# STM32F103VE.net
KiCad netlist of a schematic drawn in Altium Designer
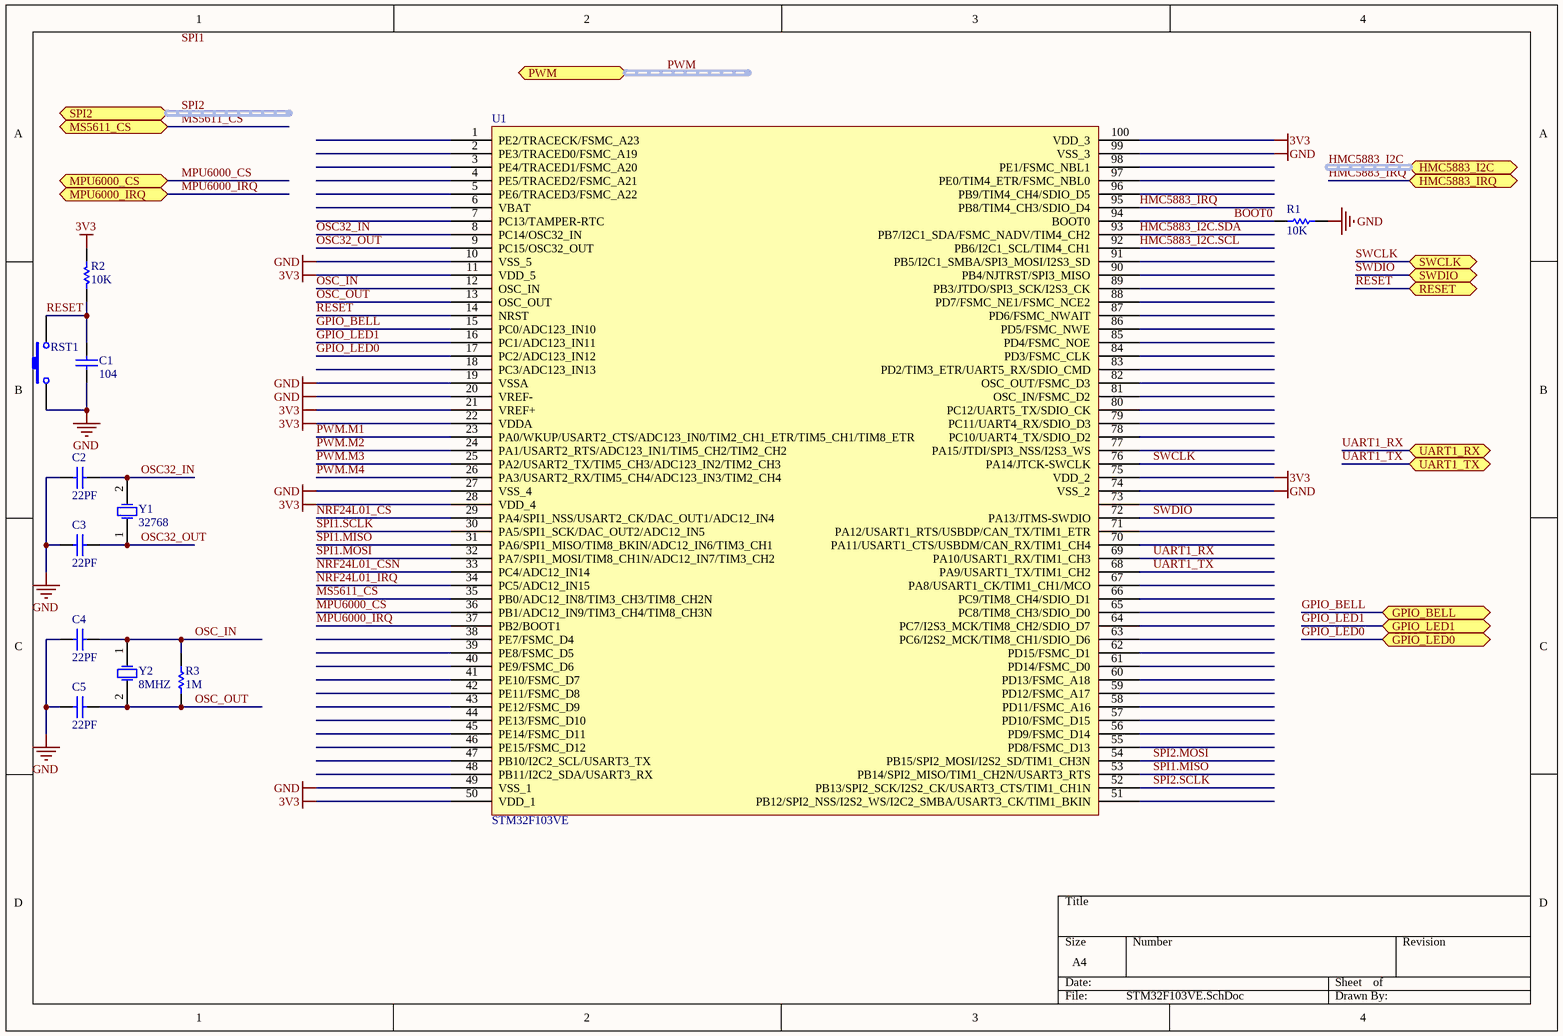
[diagram p0: STM32F103VE.SchDoc]

(export (version "E")
  (design (tool "Eeschema 10.0.6"))
  (components
    (comp (ref "C1")
      (value "104")
      (footprint "RC0805")
      (description "Capacitor")
      (fields (field (name "Comment") "Cap") (field (name "PUBLISHER") "Altium Limited"))
      (libsource (lib "Miscellaneous Devices") (part "Cap"))
    )
    (comp (ref "C2")
      (value "22PF")
      (footprint "RC0805")
      (description "Capacitor")
      (fields (field (name "Comment") "Cap") (field (name "PUBLISHER") "Altium Limited"))
      (libsource (lib "Miscellaneous Devices") (part "Cap"))
    )
    (comp (ref "C3")
      (value "22PF")
      (footprint "RC0805")
      (description "Capacitor")
      (fields (field (name "Comment") "Cap") (field (name "PUBLISHER") "Altium Limited"))
      (libsource (lib "Miscellaneous Devices") (part "Cap"))
    )
    (comp (ref "C4")
      (value "22PF")
      (footprint "RC0805")
      (description "Capacitor")
      (fields (field (name "Comment") "Cap") (field (name "PUBLISHER") "Altium Limited"))
      (libsource (lib "Miscellaneous Devices") (part "Cap"))
    )
    (comp (ref "C5")
      (value "22PF")
      (footprint "RC0805")
      (description "Capacitor")
      (fields (field (name "Comment") "Cap") (field (name "PUBLISHER") "Altium Limited"))
      (libsource (lib "Miscellaneous Devices") (part "Cap"))
    )
    (comp (ref "R1")
      (value "10K")
      (footprint "RC0805")
      (description "Resistor")
      (fields (field (name "Comment") "Res1") (field (name "PUBLISHER") "Altium Limited"))
      (libsource (lib "Miscellaneous Devices") (part "Res1"))
    )
    (comp (ref "R2")
      (value "10K")
      (footprint "RC0805")
      (description "Resistor")
      (fields (field (name "Comment") "Res1") (field (name "PUBLISHER") "Altium Limited"))
      (libsource (lib "Miscellaneous Devices") (part "Res1"))
    )
    (comp (ref "R3")
      (value "1M")
      (footprint "RC0805")
      (description "Resistor")
      (fields (field (name "Comment") "Res1") (field (name "PUBLISHER") "Altium Limited"))
      (libsource (lib "Miscellaneous Devices") (part "Res1"))
    )
    (comp (ref "RST1")
      (value "SW-PB")
      (footprint "KEY2*2(COMMON)")
      (description "Switch")
      (fields (field (name "PUBLISHER") "Altium Limited"))
      (libsource (lib "Miscellaneous Devices") (part "SW-PB"))
    )
    (comp (ref "U1") (value "STM32F103VE") (libsource (lib "Schlib1") (part "STM32F103VE")))
    (comp (ref "Y1")
      (value "32768")
      (footprint "XTAL32")
      (description "Crystal Oscillator")
      (fields (field (name "PUBLISHER") "Altium Limited"))
      (libsource (lib "Miscellaneous Devices") (part "XTAL"))
    )
    (comp (ref "Y2")
      (value "8MHZ")
      (footprint "OSC")
      (description "Crystal Oscillator")
      (fields (field (name "PUBLISHER") "Altium Limited"))
      (libsource (lib "底板封装库") (part "XTAL"))
    )
  )
  (nets
    (net (code "4") (name "/BOOT0") (class "Default")
      (node (ref "R1") (pin "2") (pinfunction "2_2") (pintype "passive"))
      (node (ref "U1") (pin "94") (pinfunction "BOOT0_94") (pintype "passive"))
    )
    (net (code "5") (name "/GPIO_BELL") (class "Default")
      (node (ref "U1") (pin "15") (pinfunction "PC0/ADC123_IN10_15") (pintype "passive"))
    )
    (net (code "6") (name "/GPIO_LED0") (class "Default")
      (node (ref "U1") (pin "17") (pinfunction "PC2/ADC123_IN12_17") (pintype "passive"))
    )
    (net (code "7") (name "/GPIO_LED1") (class "Default")
      (node (ref "U1") (pin "16") (pinfunction "PC1/ADC123_IN11_16") (pintype "passive"))
    )
    (net (code "8") (name "/HMC5883_I2C.SCL") (class "Default")
      (node (ref "U1") (pin "92") (pinfunction "PB6/I2C1_SCL/TIM4_CH1_92") (pintype "passive"))
    )
    (net (code "9") (name "/HMC5883_I2C.SDA") (class "Default")
      (node (ref "U1") (pin "93") (pinfunction "PB7/I2C1_SDA/FSMC_NADV/TIM4_CH2_93") (pintype "passive"))
    )
    (net (code "10") (name "/HMC5883_IRQ") (class "Default")
      (node (ref "U1") (pin "95") (pinfunction "PB8/TIM4_CH3/SDIO_D4_95") (pintype "passive"))
    )
    (net (code "11") (name "/MPU6000_CS") (class "Default")
      (node (ref "U1") (pin "36") (pinfunction "PB1/ADC12_IN9/TIM3_CH4/TIM8_CH3N_36") (pintype "passive"))
    )
    (net (code "12") (name "/MPU6000_IRQ") (class "Default")
      (node (ref "U1") (pin "37") (pinfunction "PB2/BOOT1_37") (pintype "passive"))
    )
    (net (code "13") (name "/MS5611_CS") (class "Default")
      (node (ref "U1") (pin "35") (pinfunction "PB0/ADC12_IN8/TIM3_CH3/TIM8_CH2N_35") (pintype "passive"))
    )
    (net (code "14") (name "/NRF24L01_CS") (class "Default")
      (node (ref "U1") (pin "29") (pinfunction "PA4/SPI1_NSS/USART2_CK/DAC_OUT1/ADC12_IN4_29") (pintype "passive"))
    )
    (net (code "15") (name "/NRF24L01_CSN") (class "Default")
      (node (ref "U1") (pin "33") (pinfunction "PC4/ADC12_IN14_33") (pintype "passive"))
    )
    (net (code "16") (name "/NRF24L01_IRQ") (class "Default")
      (node (ref "U1") (pin "34") (pinfunction "PC5/ADC12_IN15_34") (pintype "passive"))
    )
    (net (code "17") (name "/OSC32_IN") (class "Default")
      (node (ref "C2") (pin "2") (pinfunction "2_2") (pintype "passive"))
      (node (ref "U1") (pin "8") (pinfunction "PC14/OSC32_IN_8") (pintype "passive"))
      (node (ref "Y1") (pin "2") (pinfunction "OSC2_2") (pintype "passive"))
    )
    (net (code "18") (name "/OSC32_OUT") (class "Default")
      (node (ref "C3") (pin "2") (pinfunction "2_2") (pintype "passive"))
      (node (ref "U1") (pin "9") (pinfunction "PC15/OSC32_OUT_9") (pintype "passive"))
      (node (ref "Y1") (pin "1") (pinfunction "OSC1_1") (pintype "passive"))
    )
    (net (code "19") (name "/OSC_IN") (class "Default")
      (node (ref "C4") (pin "2") (pinfunction "2_2") (pintype "passive"))
      (node (ref "R3") (pin "2") (pinfunction "2_2") (pintype "passive"))
      (node (ref "U1") (pin "12") (pinfunction "OSC_IN_12") (pintype "passive"))
      (node (ref "Y2") (pin "1") (pinfunction "OSC1_1") (pintype "passive"))
    )
    (net (code "20") (name "/OSC_OUT") (class "Default")
      (node (ref "C5") (pin "2") (pinfunction "2_2") (pintype "passive"))
      (node (ref "R3") (pin "1") (pinfunction "1_1") (pintype "passive"))
      (node (ref "U1") (pin "13") (pinfunction "OSC_OUT_13") (pintype "passive"))
      (node (ref "Y2") (pin "2") (pinfunction "OSC2_2") (pintype "passive"))
    )
    (net (code "21") (name "/PWM.M1") (class "Default")
      (node (ref "U1") (pin "23") (pinfunction "PA0/WKUP/USART2_CTS/ADC123_IN0/TIM2_CH1_ETR/TIM5_CH1/TIM8_ETR_23") (pintype "passive"))
    )
    (net (code "22") (name "/PWM.M2") (class "Default")
      (node (ref "U1") (pin "24") (pinfunction "PA1/USART2_RTS/ADC123_IN1/TIM5_CH2/TIM2_CH2_24") (pintype "passive"))
    )
    (net (code "23") (name "/PWM.M3") (class "Default")
      (node (ref "U1") (pin "25") (pinfunction "PA2/USART2_TX/TIM5_CH3/ADC123_IN2/TIM2_CH3_25") (pintype "passive"))
    )
    (net (code "24") (name "/PWM.M4") (class "Default")
      (node (ref "U1") (pin "26") (pinfunction "PA3/USART2_RX/TIM5_CH4/ADC123_IN3/TIM2_CH4_26") (pintype "passive"))
    )
    (net (code "25") (name "/RESET") (class "Default")
      (node (ref "C1") (pin "1") (pinfunction "1_1") (pintype "passive"))
      (node (ref "R2") (pin "1") (pinfunction "1_1") (pintype "passive"))
      (node (ref "RST1") (pin "1") (pinfunction "1_1") (pintype "passive"))
      (node (ref "U1") (pin "14") (pinfunction "NRST_14") (pintype "passive"))
    )
    (net (code "27") (name "/SPI1.MISO") (class "Default")
      (node (ref "U1") (pin "31") (pinfunction "PA6/SPI1_MISO/TIM8_BKIN/ADC12_IN6/TIM3_CH1_31") (pintype "passive"))
      (node (ref "U1") (pin "53") (pinfunction "PB14/SPI2_MISO/TIM1_CH2N/USART3_RTS_53") (pintype "passive"))
    )
    (net (code "28") (name "/SPI1.MOSI") (class "Default")
      (node (ref "U1") (pin "32") (pinfunction "PA7/SPI1_MOSI/TIM8_CH1N/ADC12_IN7/TIM3_CH2_32") (pintype "passive"))
    )
    (net (code "29") (name "/SPI1.SCLK") (class "Default")
      (node (ref "U1") (pin "30") (pinfunction "PA5/SPI1_SCK/DAC_OUT2/ADC12_IN5_30") (pintype "passive"))
    )
    (net (code "30") (name "/SPI2.MOSI") (class "Default")
      (node (ref "U1") (pin "54") (pinfunction "PB15/SPI2_MOSI/I2S2_SD/TIM1_CH3N_54") (pintype "passive"))
    )
    (net (code "31") (name "/SPI2.SCLK") (class "Default")
      (node (ref "U1") (pin "52") (pinfunction "PB13/SPI2_SCK/I2S2_CK/USART3_CTS/TIM1_CH1N_52") (pintype "passive"))
    )
    (net (code "32") (name "/SWCLK") (class "Default")
      (node (ref "U1") (pin "76") (pinfunction "PA14/JTCK-SWCLK_76") (pintype "passive"))
    )
    (net (code "33") (name "/SWDIO") (class "Default")
      (node (ref "U1") (pin "72") (pinfunction "PA13/JTMS-SWDIO_72") (pintype "passive"))
    )
    (net (code "34") (name "/UART1_RX") (class "Default")
      (node (ref "U1") (pin "69") (pinfunction "PA10/USART1_RX/TIM1_CH3_69") (pintype "passive"))
    )
    (net (code "35") (name "/UART1_TX") (class "Default")
      (node (ref "U1") (pin "68") (pinfunction "PA9/USART1_TX/TIM1_CH2_68") (pintype "passive"))
    )
    (net (code "39") (name "3V3") (class "Default")
      (node (ref "R2") (pin "2") (pinfunction "2_2") (pintype "passive"))
      (node (ref "U1") (pin "100") (pinfunction "VDD_3_100") (pintype "passive"))
      (node (ref "U1") (pin "11") (pinfunction "VDD_5_11") (pintype "passive"))
      (node (ref "U1") (pin "21") (pinfunction "VREF+_21") (pintype "passive"))
      (node (ref "U1") (pin "22") (pinfunction "VDDA_22") (pintype "passive"))
      (node (ref "U1") (pin "28") (pinfunction "VDD_4_28") (pintype "passive"))
      (node (ref "U1") (pin "50") (pinfunction "VDD_1_50") (pintype "passive"))
      (node (ref "U1") (pin "75") (pinfunction "VDD_2_75") (pintype "passive"))
    )
    (net (code "40") (name "GND") (class "Default")
      (node (ref "C1") (pin "2") (pinfunction "2_2") (pintype "passive"))
      (node (ref "C2") (pin "1") (pinfunction "1_1") (pintype "passive"))
      (node (ref "C3") (pin "1") (pinfunction "1_1") (pintype "passive"))
      (node (ref "C4") (pin "1") (pinfunction "1_1") (pintype "passive"))
      (node (ref "C5") (pin "1") (pinfunction "1_1") (pintype "passive"))
      (node (ref "R1") (pin "1") (pinfunction "1_1") (pintype "passive"))
      (node (ref "RST1") (pin "2") (pinfunction "2_2") (pintype "passive"))
      (node (ref "U1") (pin "10") (pinfunction "VSS_5_10") (pintype "passive"))
      (node (ref "U1") (pin "19") (pinfunction "VSSA_19") (pintype "passive"))
      (node (ref "U1") (pin "20") (pinfunction "VREF-_20") (pintype "passive"))
      (node (ref "U1") (pin "27") (pinfunction "VSS_4_27") (pintype "passive"))
      (node (ref "U1") (pin "49") (pinfunction "VSS_1_49") (pintype "passive"))
      (node (ref "U1") (pin "74") (pinfunction "VSS_2_74") (pintype "passive"))
      (node (ref "U1") (pin "99") (pinfunction "VSS_3_99") (pintype "passive"))
    )
    (net (code "41") (name "unconnected-(U1-OSC_IN{slash}FSMC_D2-Pad81)") (class "Default")
      (node (ref "U1") (pin "81") (pinfunction "OSC_IN/FSMC_D2_81") (pintype "passive"))
    )
    (net (code "42") (name "unconnected-(U1-OSC_OUT{slash}FSMC_D3-Pad82)") (class "Default")
      (node (ref "U1") (pin "82") (pinfunction "OSC_OUT/FSMC_D3_82") (pintype "passive"))
    )
    (net (code "43") (name "unconnected-(U1-PA8{slash}USART1_CK{slash}TIM1_CH1{slash}MCO-Pad67)") (class "Default")
      (node (ref "U1") (pin "67") (pinfunction "PA8/USART1_CK/TIM1_CH1/MCO_67") (pintype "passive"))
    )
    (net (code "44") (name "unconnected-(U1-PA11{slash}USART1_CTS{slash}USBDM{slash}CAN_RX{slash}TIM1_CH4-Pad70)") (class "Default")
      (node (ref "U1") (pin "70") (pinfunction "PA11/USART1_CTS/USBDM/CAN_RX/TIM1_CH4_70") (pintype "passive"))
    )
    (net (code "45") (name "unconnected-(U1-PA12{slash}USART1_RTS{slash}USBDP{slash}CAN_TX{slash}TIM1_ETR-Pad71)") (class "Default")
      (node (ref "U1") (pin "71") (pinfunction "PA12/USART1_RTS/USBDP/CAN_TX/TIM1_ETR_71") (pintype "passive"))
    )
    (net (code "46") (name "unconnected-(U1-PA15{slash}JTDI{slash}SPI3_NSS{slash}I2S3_WS-Pad77)") (class "Default")
      (node (ref "U1") (pin "77") (pinfunction "PA15/JTDI/SPI3_NSS/I2S3_WS_77") (pintype "passive"))
    )
    (net (code "47") (name "unconnected-(U1-PB3{slash}JTDO{slash}SPI3_SCK{slash}I2S3_CK-Pad89)") (class "Default")
      (node (ref "U1") (pin "89") (pinfunction "PB3/JTDO/SPI3_SCK/I2S3_CK_89") (pintype "passive"))
    )
    (net (code "48") (name "unconnected-(U1-PB4{slash}NJTRST{slash}SPI3_MISO-Pad90)") (class "Default")
      (node (ref "U1") (pin "90") (pinfunction "PB4/NJTRST/SPI3_MISO_90") (pintype "passive"))
    )
    (net (code "49") (name "unconnected-(U1-PB5{slash}I2C1_SMBA{slash}SPI3_MOSI{slash}I2S3_SD-Pad91)") (class "Default")
      (node (ref "U1") (pin "91") (pinfunction "PB5/I2C1_SMBA/SPI3_MOSI/I2S3_SD_91") (pintype "passive"))
    )
    (net (code "50") (name "unconnected-(U1-PB9{slash}TIM4_CH4{slash}SDIO_D5-Pad96)") (class "Default")
      (node (ref "U1") (pin "96") (pinfunction "PB9/TIM4_CH4/SDIO_D5_96") (pintype "passive"))
    )
    (net (code "51") (name "unconnected-(U1-PB10{slash}I2C2_SCL{slash}USART3_TX-Pad47)") (class "Default")
      (node (ref "U1") (pin "47") (pinfunction "PB10/I2C2_SCL/USART3_TX_47") (pintype "passive"))
    )
    (net (code "52") (name "unconnected-(U1-PB11{slash}I2C2_SDA{slash}USART3_RX-Pad48)") (class "Default")
      (node (ref "U1") (pin "48") (pinfunction "PB11/I2C2_SDA/USART3_RX_48") (pintype "passive"))
    )
    (net (code "53") (name "unconnected-(U1-PB12{slash}SPI2_NSS{slash}I2S2_WS{slash}I2C2_SMBA{slash}USART3_CK{slash}TIM1_BKIN-Pad51)") (class "Default")
      (node (ref "U1") (pin "51") (pinfunction "PB12/SPI2_NSS/I2S2_WS/I2C2_SMBA/USART3_CK/TIM1_BKIN_51") (pintype "passive"))
    )
    (net (code "54") (name "unconnected-(U1-PC3{slash}ADC123_IN13-Pad18)") (class "Default")
      (node (ref "U1") (pin "18") (pinfunction "PC3/ADC123_IN13_18") (pintype "passive"))
    )
    (net (code "55") (name "unconnected-(U1-PC6{slash}I2S2_MCK{slash}TIM8_CH1{slash}SDIO_D6-Pad63)") (class "Default")
      (node (ref "U1") (pin "63") (pinfunction "PC6/I2S2_MCK/TIM8_CH1/SDIO_D6_63") (pintype "passive"))
    )
    (net (code "56") (name "unconnected-(U1-PC7{slash}I2S3_MCK{slash}TIM8_CH2{slash}SDIO_D7-Pad64)") (class "Default")
      (node (ref "U1") (pin "64") (pinfunction "PC7/I2S3_MCK/TIM8_CH2/SDIO_D7_64") (pintype "passive"))
    )
    (net (code "57") (name "unconnected-(U1-PC8{slash}TIM8_CH3{slash}SDIO_D0-Pad65)") (class "Default")
      (node (ref "U1") (pin "65") (pinfunction "PC8/TIM8_CH3/SDIO_D0_65") (pintype "passive"))
    )
    (net (code "58") (name "unconnected-(U1-PC9{slash}TIM8_CH4{slash}SDIO_D1-Pad66)") (class "Default")
      (node (ref "U1") (pin "66") (pinfunction "PC9/TIM8_CH4/SDIO_D1_66") (pintype "passive"))
    )
    (net (code "59") (name "unconnected-(U1-PC10{slash}UART4_TX{slash}SDIO_D2-Pad78)") (class "Default")
      (node (ref "U1") (pin "78") (pinfunction "PC10/UART4_TX/SDIO_D2_78") (pintype "passive"))
    )
    (net (code "60") (name "unconnected-(U1-PC11{slash}UART4_RX{slash}SDIO_D3-Pad79)") (class "Default")
      (node (ref "U1") (pin "79") (pinfunction "PC11/UART4_RX/SDIO_D3_79") (pintype "passive"))
    )
    (net (code "61") (name "unconnected-(U1-PC12{slash}UART5_TX{slash}SDIO_CK-Pad80)") (class "Default")
      (node (ref "U1") (pin "80") (pinfunction "PC12/UART5_TX/SDIO_CK_80") (pintype "passive"))
    )
    (net (code "62") (name "unconnected-(U1-PC13{slash}TAMPER-RTC-Pad7)") (class "Default")
      (node (ref "U1") (pin "7") (pinfunction "PC13/TAMPER-RTC_7") (pintype "passive"))
    )
    (net (code "63") (name "unconnected-(U1-PD2{slash}TIM3_ETR{slash}UART5_RX{slash}SDIO_CMD-Pad83)") (class "Default")
      (node (ref "U1") (pin "83") (pinfunction "PD2/TIM3_ETR/UART5_RX/SDIO_CMD_83") (pintype "passive"))
    )
    (net (code "64") (name "unconnected-(U1-PD3{slash}FSMC_CLK-Pad84)") (class "Default")
      (node (ref "U1") (pin "84") (pinfunction "PD3/FSMC_CLK_84") (pintype "passive"))
    )
    (net (code "65") (name "unconnected-(U1-PD4{slash}FSMC_NOE-Pad85)") (class "Default")
      (node (ref "U1") (pin "85") (pinfunction "PD4/FSMC_NOE_85") (pintype "passive"))
    )
    (net (code "66") (name "unconnected-(U1-PD5{slash}FSMC_NWE-Pad86)") (class "Default")
      (node (ref "U1") (pin "86") (pinfunction "PD5/FSMC_NWE_86") (pintype "passive"))
    )
    (net (code "67") (name "unconnected-(U1-PD6{slash}FSMC_NWAIT-Pad87)") (class "Default")
      (node (ref "U1") (pin "87") (pinfunction "PD6/FSMC_NWAIT_87") (pintype "passive"))
    )
    (net (code "68") (name "unconnected-(U1-PD7{slash}FSMC_NE1{slash}FSMC_NCE2-Pad88)") (class "Default")
      (node (ref "U1") (pin "88") (pinfunction "PD7/FSMC_NE1/FSMC_NCE2_88") (pintype "passive"))
    )
    (net (code "69") (name "unconnected-(U1-PD8{slash}FSMC_D13-Pad55)") (class "Default")
      (node (ref "U1") (pin "55") (pinfunction "PD8/FSMC_D13_55") (pintype "passive"))
    )
    (net (code "70") (name "unconnected-(U1-PD9{slash}FSMC_D14-Pad56)") (class "Default")
      (node (ref "U1") (pin "56") (pinfunction "PD9/FSMC_D14_56") (pintype "passive"))
    )
    (net (code "71") (name "unconnected-(U1-PD10{slash}FSMC_D15-Pad57)") (class "Default")
      (node (ref "U1") (pin "57") (pinfunction "PD10/FSMC_D15_57") (pintype "passive"))
    )
    (net (code "72") (name "unconnected-(U1-PD11{slash}FSMC_A16-Pad58)") (class "Default")
      (node (ref "U1") (pin "58") (pinfunction "PD11/FSMC_A16_58") (pintype "passive"))
    )
    (net (code "73") (name "unconnected-(U1-PD12{slash}FSMC_A17-Pad59)") (class "Default")
      (node (ref "U1") (pin "59") (pinfunction "PD12/FSMC_A17_59") (pintype "passive"))
    )
    (net (code "74") (name "unconnected-(U1-PD13{slash}FSMC_A18-Pad60)") (class "Default")
      (node (ref "U1") (pin "60") (pinfunction "PD13/FSMC_A18_60") (pintype "passive"))
    )
    (net (code "75") (name "unconnected-(U1-PD14{slash}FSMC_D0-Pad61)") (class "Default")
      (node (ref "U1") (pin "61") (pinfunction "PD14/FSMC_D0_61") (pintype "passive"))
    )
    (net (code "76") (name "unconnected-(U1-PD15{slash}FSMC_D1-Pad62)") (class "Default")
      (node (ref "U1") (pin "62") (pinfunction "PD15/FSMC_D1_62") (pintype "passive"))
    )
    (net (code "77") (name "unconnected-(U1-PE0{slash}TIM4_ETR{slash}FSMC_NBL0-Pad97)") (class "Default")
      (node (ref "U1") (pin "97") (pinfunction "PE0/TIM4_ETR/FSMC_NBL0_97") (pintype "passive"))
    )
    (net (code "78") (name "unconnected-(U1-PE1{slash}FSMC_NBL1-Pad98)") (class "Default")
      (node (ref "U1") (pin "98") (pinfunction "PE1/FSMC_NBL1_98") (pintype "passive"))
    )
    (net (code "79") (name "unconnected-(U1-PE2{slash}TRACECK{slash}FSMC_A23-Pad1)") (class "Default")
      (node (ref "U1") (pin "1") (pinfunction "PE2/TRACECK/FSMC_A23_1") (pintype "passive"))
    )
    (net (code "80") (name "unconnected-(U1-PE3{slash}TRACED0{slash}FSMC_A19-Pad2)") (class "Default")
      (node (ref "U1") (pin "2") (pinfunction "PE3/TRACED0/FSMC_A19_2") (pintype "passive"))
    )
    (net (code "81") (name "unconnected-(U1-PE4{slash}TRACED1{slash}FSMC_A20-Pad3)") (class "Default")
      (node (ref "U1") (pin "3") (pinfunction "PE4/TRACED1/FSMC_A20_3") (pintype "passive"))
    )
    (net (code "82") (name "unconnected-(U1-PE5{slash}TRACED2{slash}FSMC_A21-Pad4)") (class "Default")
      (node (ref "U1") (pin "4") (pinfunction "PE5/TRACED2/FSMC_A21_4") (pintype "passive"))
    )
    (net (code "83") (name "unconnected-(U1-PE6{slash}TRACED3{slash}FSMC_A22-Pad5)") (class "Default")
      (node (ref "U1") (pin "5") (pinfunction "PE6/TRACED3/FSMC_A22_5") (pintype "passive"))
    )
    (net (code "84") (name "unconnected-(U1-PE7{slash}FSMC_D4-Pad38)") (class "Default")
      (node (ref "U1") (pin "38") (pinfunction "PE7/FSMC_D4_38") (pintype "passive"))
    )
    (net (code "85") (name "unconnected-(U1-PE8{slash}FSMC_D5-Pad39)") (class "Default")
      (node (ref "U1") (pin "39") (pinfunction "PE8/FSMC_D5_39") (pintype "passive"))
    )
    (net (code "86") (name "unconnected-(U1-PE9{slash}FSMC_D6-Pad40)") (class "Default")
      (node (ref "U1") (pin "40") (pinfunction "PE9/FSMC_D6_40") (pintype "passive"))
    )
    (net (code "87") (name "unconnected-(U1-PE10{slash}FSMC_D7-Pad41)") (class "Default")
      (node (ref "U1") (pin "41") (pinfunction "PE10/FSMC_D7_41") (pintype "passive"))
    )
    (net (code "88") (name "unconnected-(U1-PE11{slash}FSMC_D8-Pad42)") (class "Default")
      (node (ref "U1") (pin "42") (pinfunction "PE11/FSMC_D8_42") (pintype "passive"))
    )
    (net (code "89") (name "unconnected-(U1-PE12{slash}FSMC_D9-Pad43)") (class "Default")
      (node (ref "U1") (pin "43") (pinfunction "PE12/FSMC_D9_43") (pintype "passive"))
    )
    (net (code "90") (name "unconnected-(U1-PE13{slash}FSMC_D10-Pad44)") (class "Default")
      (node (ref "U1") (pin "44") (pinfunction "PE13/FSMC_D10_44") (pintype "passive"))
    )
    (net (code "91") (name "unconnected-(U1-PE14{slash}FSMC_D11-Pad45)") (class "Default")
      (node (ref "U1") (pin "45") (pinfunction "PE14/FSMC_D11_45") (pintype "passive"))
    )
    (net (code "92") (name "unconnected-(U1-PE15{slash}FSMC_D12-Pad46)") (class "Default")
      (node (ref "U1") (pin "46") (pinfunction "PE15/FSMC_D12_46") (pintype "passive"))
    )
    (net (code "93") (name "unconnected-(U1-Pad73)") (class "Default")
      (node (ref "U1") (pin "73") (pintype "passive"))
    )
    (net (code "94") (name "unconnected-(U1-VBAT-Pad6)") (class "Default")
      (node (ref "U1") (pin "6") (pinfunction "VBAT_6") (pintype "passive"))
    )
  )
)
